# PR9026.net
KiCad netlist of a schematic drawn in EAGLE
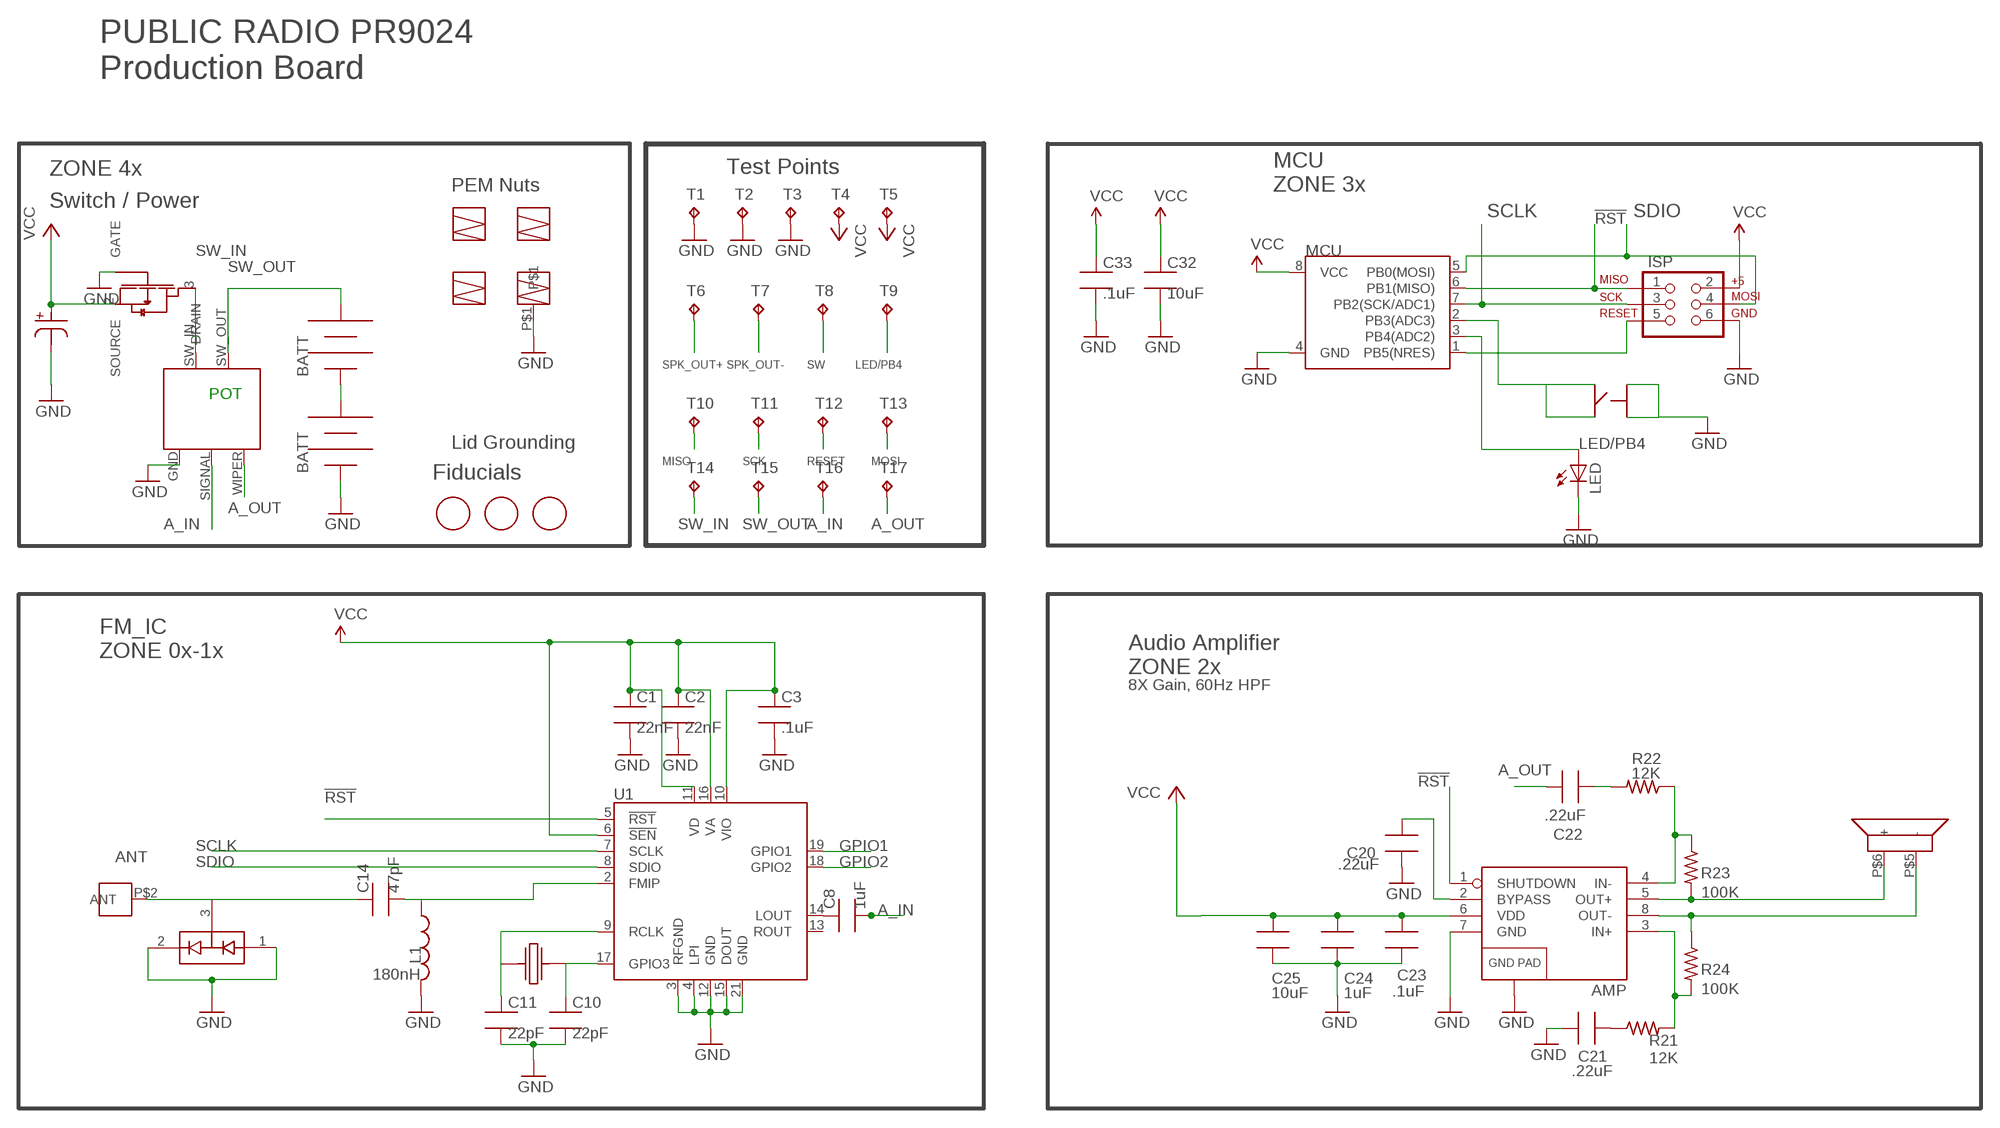
[diagram p0: schematic, sheet 1]

(export (version "E")
  (design (tool "Eeschema 10.0.6"))
  (components
    (comp (ref "AMP")
      (value "TPA6203A1")
      (footprint "eagle-import:8-MSOP")
      (libsource (lib "eagle-import") (part "TPA6203A1"))
    )
    (comp (ref "ANT_MOUNT")
      (value "DNP")
      (footprint "eagle-import:PEM_M3")
      (libsource (lib "eagle-import") (part "M3_PEMNUT"))
    )
    (comp (ref "C1")
      (value "22nF")
      (footprint "eagle-import:0603_CPL")
      (fields
        (field (name "MFG_PN") "CL10B223KB8NNNC")
        (field (name "TOL") "10%")
        (field (name "VOLTAGE") "16V")
      )
      (libsource (lib "eagle-import") (part "C_SMT_0603_CPL"))
    )
    (comp (ref "C2")
      (value "22nF")
      (footprint "eagle-import:0603_CPL")
      (fields
        (field (name "MFG_PN") "CL10B223KB8NNNC")
        (field (name "TOL") "10%")
        (field (name "VOLTAGE") "16V")
      )
      (libsource (lib "eagle-import") (part "C_SMT_0603_CPL"))
    )
    (comp (ref "C3")
      (value ".1uF")
      (footprint "eagle-import:0603_CPL")
      (fields
        (field (name "MFG_PN") "CL10B104KB8SFNC")
        (field (name "TOL") "10%")
        (field (name "VOLTAGE") "16V")
      )
      (libsource (lib "eagle-import") (part "C_SMT_0603_CPL"))
    )
    (comp (ref "C8")
      (value "1uF")
      (footprint "eagle-import:0603_CPL")
      (fields
        (field (name "MFG_PN") "CL10B105KP8NNNC")
        (field (name "TOL") "10%")
        (field (name "VOLTAGE") "10V")
      )
      (libsource (lib "eagle-import") (part "C_SMT_0603_CPL"))
    )
    (comp (ref "C10")
      (value "22pF")
      (footprint "eagle-import:0603_CPL")
      (fields
        (field (name "MFG_PN") "C1608C0G1H220J080AA")
        (field (name "TOL") "5%")
        (field (name "VOLTAGE") "50V")
      )
      (libsource (lib "eagle-import") (part "C_SMT_0603_CPL"))
    )
    (comp (ref "C11")
      (value "22pF")
      (footprint "eagle-import:0603_CPL")
      (fields
        (field (name "MFG_PN") "C1608C0G1H220J080AA")
        (field (name "TOL") "5%")
        (field (name "VOLTAGE") "50V")
      )
      (libsource (lib "eagle-import") (part "C_SMT_0603_CPL"))
    )
    (comp (ref "C14")
      (value "47pF")
      (footprint "eagle-import:0603_CPL")
      (fields
        (field (name "MFG_PN") "CL10C470JB8NCNC")
        (field (name "TOL") "5%")
        (field (name "VOLTAGE") "50V")
      )
      (libsource (lib "eagle-import") (part "C_SMT_0603_CPL"))
    )
    (comp (ref "C20")
      (value ".22uF")
      (footprint "eagle-import:0603_CPL")
      (fields
        (field (name "MFG_PN") "C1608X7R1C224K080AC")
        (field (name "TOL") "10%")
        (field (name "VOLTAGE") "16V")
      )
      (libsource (lib "eagle-import") (part "C_SMT_0603_CPL"))
    )
    (comp (ref "C21")
      (value ".22uF")
      (footprint "eagle-import:0603_CPL")
      (fields
        (field (name "MFG_PN") "C1608X7R1C224K080AC")
        (field (name "TOL") "10%")
        (field (name "VOLTAGE") "16V")
      )
      (libsource (lib "eagle-import") (part "C_SMT_0603_CPL"))
    )
    (comp (ref "C22")
      (value ".22uF")
      (footprint "eagle-import:0603_CPL")
      (fields
        (field (name "MFG_PN") "C1608X7R1C224K080AC")
        (field (name "TOL") "10%")
        (field (name "VOLTAGE") "16V")
      )
      (libsource (lib "eagle-import") (part "C_SMT_0603_CPL"))
    )
    (comp (ref "C23")
      (value ".1uF")
      (footprint "eagle-import:0603_CPL")
      (fields
        (field (name "MFG_PN") "CL10B104KB8SFNC")
        (field (name "TOL") "10%")
        (field (name "VOLTAGE") "16V")
      )
      (libsource (lib "eagle-import") (part "C_SMT_0603_CPL"))
    )
    (comp (ref "C24")
      (value "1uF")
      (footprint "eagle-import:0603_CPL")
      (fields
        (field (name "MFG_PN") "CL10B105KP8NNNC")
        (field (name "TOL") "10%")
        (field (name "VOLTAGE") "10V")
      )
      (libsource (lib "eagle-import") (part "C_SMT_0603_CPL"))
    )
    (comp (ref "C25")
      (value "10uF")
      (footprint "eagle-import:0603_CPL")
      (fields
        (field (name "MFG_PN") "CL10A106MQ8NNNC")
        (field (name "TOL") "20%")
        (field (name "VOLTAGE") "6.3V")
      )
      (libsource (lib "eagle-import") (part "C_SMT_0603_CPL"))
    )
    (comp (ref "C32")
      (value "10uF")
      (footprint "eagle-import:0603_CPL")
      (fields
        (field (name "MFG_PN") "CL10A106MQ8NNNC")
        (field (name "TOL") "20%")
        (field (name "VOLTAGE") "6.3V")
      )
      (libsource (lib "eagle-import") (part "C_SMT_0603_CPL"))
    )
    (comp (ref "C33")
      (value ".1uF")
      (footprint "eagle-import:0603_CPL")
      (fields
        (field (name "MFG_PN") "CL10B104KB8SFNC")
        (field (name "TOL") "10%")
        (field (name "VOLTAGE") "16V")
      )
      (libsource (lib "eagle-import") (part "C_SMT_0603_CPL"))
    )
    (comp (ref "C40")
      (value "220uF")
      (footprint "eagle-import:NICHICON_UD_63")
      (fields (field (name "TOL") "20%") (field (name "VOLTAGE") "16V"))
      (libsource (lib "eagle-import") (part "NICHICON_SERIESUD"))
    )
    (comp (ref "D1")
      (value "BAV99")
      (footprint "eagle-import:SOT23_CPL")
      (fields (field (name "MFG_PN") "BAV99,215"))
      (libsource (lib "eagle-import") (part "BAV99"))
    )
    (comp (ref "FET1")
      (value "AO3435")
      (footprint "eagle-import:SOT23_CPL")
      (fields (field (name "MFG_PN") "AO3435"))
      (libsource (lib "eagle-import") (part "AO3435"))
    )
    (comp (ref "ISP")
      (value "AVR_SPI_PRG_6NS")
      (footprint "eagle-import:2X3-NS")
      (libsource (lib "eagle-import") (part "AVR_SPI_PRG_6NS"))
    )
    (comp (ref "JP5")
      (value "BK-92_MPD_AA_BATT_CLIP")
      (footprint "eagle-import:BK92_AA_BATT")
      (fields (field (name "MFG_PN") "2 of BK92 - supplied by CL Labs"))
      (libsource (lib "eagle-import") (part "BK-92_MPD_AA_BATT_CLIP"))
    )
    (comp (ref "JP6")
      (value "BK-92_MPD_AA_BATT_CLIP")
      (footprint "eagle-import:BK92_AA_BATT")
      (fields (field (name "MFG_PN") "2 of BK92 - supplied by CL Labs"))
      (libsource (lib "eagle-import") (part "BK-92_MPD_AA_BATT_CLIP"))
    )
    (comp (ref "L1")
      (value "180nH")
      (footprint "eagle-import:0805_ADAFRUIT")
      (fields
        (field (name "CURRENT") "400mA")
        (field (name "DCR") "640m")
        (field (name "MFG_PN") "AISC-0805-R18J-T")
        (field (name "TOL") "5%")
      )
      (libsource (lib "eagle-import") (part "L_SMT_0805_ADAFRUIT"))
    )
    (comp (ref "LED")
      (value "HSMC-C265_REVERSE_MOUNT_LED")
      (footprint "eagle-import:HSMC-C265_REVERSE_MOUN_LED")
      (libsource (lib "eagle-import") (part "HSMC-C265_REVERSE_MOUNT_LED"))
    )
    (comp (ref "MARK1")
      (value "FIDUCIAL")
      (footprint "eagle-import:FIDUCIAL_1MM")
      (libsource (lib "eagle-import") (part "FIDUCIAL"))
    )
    (comp (ref "MARK2")
      (value "FIDUCIAL")
      (footprint "eagle-import:FIDUCIAL_1MM")
      (libsource (lib "eagle-import") (part "FIDUCIAL"))
    )
    (comp (ref "MARK3")
      (value "FIDUCIAL")
      (footprint "eagle-import:FIDUCIAL_1MM")
      (libsource (lib "eagle-import") (part "FIDUCIAL"))
    )
    (comp (ref "MCU")
      (value "ATTINY45TINY45-20-SMT")
      (footprint "eagle-import:8-SOIC")
      (libsource (lib "eagle-import") (part "ATTINY45TINY45-20-SMT"))
    )
    (comp (ref "R1")
      (value "VOLUME_POT")
      (footprint "eagle-import:H17112NS_A10K_L20F-002")
      (libsource (lib "eagle-import") (part "VOLUME_POT"))
    )
    (comp (ref "R21")
      (value "12K")
      (footprint "eagle-import:0603_CPL")
      (fields
        (field (name "MFG_PN") "RC0603FR-0712KL")
        (field (name "POWER") "1/10W")
        (field (name "TOL") "1%")
      )
      (libsource (lib "eagle-import") (part "R_SMT_R0603_CPL"))
    )
    (comp (ref "R22")
      (value "12K")
      (footprint "eagle-import:0603_CPL")
      (fields
        (field (name "MFG_PN") "RC0603FR-0712KL")
        (field (name "POWER") "1/10W")
        (field (name "TOL") "1%")
      )
      (libsource (lib "eagle-import") (part "R_SMT_R0603_CPL"))
    )
    (comp (ref "R23")
      (value "100K")
      (footprint "eagle-import:0603_CPL")
      (fields
        (field (name "MFG_PN") "ERJ-3EKF1003V")
        (field (name "POWER") "1/10W")
        (field (name "TOL") "1%")
      )
      (libsource (lib "eagle-import") (part "R_SMT_R0603_CPL"))
    )
    (comp (ref "R24")
      (value "100K")
      (footprint "eagle-import:0603_CPL")
      (fields
        (field (name "MFG_PN") "ERJ-3EKF1003V")
        (field (name "POWER") "1/10W")
        (field (name "TOL") "1%")
      )
      (libsource (lib "eagle-import") (part "R_SMT_R0603_CPL"))
    )
    (comp (ref "SPKR_PLACE")
      (value "PR2024_SPKR_SMD")
      (footprint "eagle-import:PR2024_SPKR_PLACE(SMD)")
      (libsource (lib "eagle-import") (part "PR2024_SPKR_SMD"))
    )
    (comp (ref "SW1")
      (value "C&K_PTS645")
      (footprint "eagle-import:C&K_PTS645_SMT")
      (libsource (lib "eagle-import") (part "C&K_PTS645"))
    )
    (comp (ref "T1")
      (value "TPTP20R")
      (footprint "eagle-import:TP20R")
      (libsource (lib "eagle-import") (part "TPTP20R"))
    )
    (comp (ref "T2")
      (value "TPTP20R")
      (footprint "eagle-import:TP20R")
      (libsource (lib "eagle-import") (part "TPTP20R"))
    )
    (comp (ref "T3")
      (value "TPTP20R")
      (footprint "eagle-import:TP20R")
      (libsource (lib "eagle-import") (part "TPTP20R"))
    )
    (comp (ref "T4")
      (value "TPTP20R")
      (footprint "eagle-import:TP20R")
      (libsource (lib "eagle-import") (part "TPTP20R"))
    )
    (comp (ref "T5")
      (value "TPTP20R")
      (footprint "eagle-import:TP20R")
      (libsource (lib "eagle-import") (part "TPTP20R"))
    )
    (comp (ref "T6")
      (value "TPTP20R")
      (footprint "eagle-import:TP20R")
      (libsource (lib "eagle-import") (part "TPTP20R"))
    )
    (comp (ref "T7")
      (value "TPTP20R")
      (footprint "eagle-import:TP20R")
      (libsource (lib "eagle-import") (part "TPTP20R"))
    )
    (comp (ref "T8")
      (value "TPTP20R")
      (footprint "eagle-import:TP20R")
      (libsource (lib "eagle-import") (part "TPTP20R"))
    )
    (comp (ref "T9")
      (value "TPTP20R")
      (footprint "eagle-import:TP20R")
      (libsource (lib "eagle-import") (part "TPTP20R"))
    )
    (comp (ref "T10")
      (value "TPTP20R")
      (footprint "eagle-import:TP20R")
      (libsource (lib "eagle-import") (part "TPTP20R"))
    )
    (comp (ref "T11")
      (value "TPTP20R")
      (footprint "eagle-import:TP20R")
      (libsource (lib "eagle-import") (part "TPTP20R"))
    )
    (comp (ref "T12")
      (value "TPTP20R")
      (footprint "eagle-import:TP20R")
      (libsource (lib "eagle-import") (part "TPTP20R"))
    )
    (comp (ref "T13")
      (value "TPTP20R")
      (footprint "eagle-import:TP20R")
      (libsource (lib "eagle-import") (part "TPTP20R"))
    )
    (comp (ref "T14")
      (value "TPTP20R")
      (footprint "eagle-import:TP20R")
      (libsource (lib "eagle-import") (part "TPTP20R"))
    )
    (comp (ref "T15")
      (value "TPTP20R")
      (footprint "eagle-import:TP20R")
      (libsource (lib "eagle-import") (part "TPTP20R"))
    )
    (comp (ref "T16")
      (value "TPTP20R")
      (footprint "eagle-import:TP20R")
      (libsource (lib "eagle-import") (part "TPTP20R"))
    )
    (comp (ref "T17")
      (value "TPTP20R")
      (footprint "eagle-import:TP20R")
      (libsource (lib "eagle-import") (part "TPTP20R"))
    )
    (comp (ref "U$2")
      (value "PEM_SMT")
      (footprint "eagle-import:PEM_SMT")
      (libsource (lib "eagle-import") (part "PEM_SMT"))
    )
    (comp (ref "U$3")
      (value "PEM_SMT")
      (footprint "eagle-import:PEM_SMT")
      (libsource (lib "eagle-import") (part "PEM_SMT"))
    )
    (comp (ref "U$4")
      (value "PEM_SMT")
      (footprint "eagle-import:PEM_SMT")
      (libsource (lib "eagle-import") (part "PEM_SMT"))
    )
    (comp (ref "U$5")
      (value "PEM_M3_SMT_W/PIN")
      (footprint "eagle-import:PEM_SMT")
      (libsource (lib "eagle-import") (part "PEM_M3_SMT_W/PIN"))
    )
    (comp (ref "U1")
      (value "SI4702-C19-GMR")
      (footprint "eagle-import:SI470X_20_QFN")
      (fields (field (name "MFG_PN") "Si4702 C19 GM - supplied by CL Labs"))
      (libsource (lib "eagle-import") (part "SI4702-C19-GMR"))
    )
    (comp (ref "X1")
      (value "ABS25XTAL")
      (footprint "eagle-import:4-SOJ")
      (libsource (lib "eagle-import") (part "ABS25XTAL"))
    )
  )
  (nets
    (net (code "1") (name "/ANT") (class "Default")
      (node (ref "ANT_MOUNT") (pin "P$2") (pinfunction "ANT_P$2") (pintype "bidirectional"))
      (node (ref "C14") (pin "1") (pinfunction "1_1") (pintype "passive"))
      (node (ref "D1") (pin "3") (pinfunction "COM_3") (pintype "bidirectional"))
    )
    (net (code "2") (name "/A_IN") (class "Default")
      (node (ref "C8") (pin "2") (pinfunction "2_2") (pintype "passive"))
      (node (ref "R1") (pin "SIGNAL") (pinfunction "SIGNAL_SIGNAL") (pintype "bidirectional"))
      (node (ref "T16") (pin "TP") (pinfunction "TP_TP") (pintype "input"))
    )
    (net (code "3") (name "/A_OUT") (class "Default")
      (node (ref "C22") (pin "2") (pinfunction "2_2") (pintype "passive"))
      (node (ref "R1") (pin "WIPER") (pinfunction "WIPER_WIPER") (pintype "bidirectional"))
      (node (ref "T17") (pin "TP") (pinfunction "TP_TP") (pintype "input"))
    )
    (net (code "4") (name "/GPIO1") (class "Default")
      (node (ref "U1") (pin "19") (pinfunction "GPIO1_19") (pintype "bidirectional"))
    )
    (net (code "5") (name "/GPIO2") (class "Default")
      (node (ref "U1") (pin "18") (pinfunction "GPIO2_18") (pintype "bidirectional"))
    )
    (net (code "6") (name "/LED{slash}PB4") (class "Default")
      (node (ref "LED") (pin "P$1") (pinfunction "A_P$1") (pintype "passive"))
      (node (ref "MCU") (pin "3") (pinfunction "PB4(ADC2)_3") (pintype "bidirectional"))
      (node (ref "T9") (pin "TP") (pinfunction "TP_TP") (pintype "input"))
    )
    (net (code "7") (name "/RESET") (class "Default")
      (node (ref "ISP") (pin "5") (pinfunction "5_5") (pintype "passive"))
      (node (ref "MCU") (pin "1") (pinfunction "PB5(NRES)_1") (pintype "bidirectional"))
      (node (ref "T12") (pin "TP") (pinfunction "TP_TP") (pintype "input"))
    )
    (net (code "8") (name "/SCLK") (class "Default")
      (node (ref "ISP") (pin "3") (pinfunction "3_3") (pintype "passive"))
      (node (ref "MCU") (pin "7") (pinfunction "PB2(SCK/ADC1)_7") (pintype "bidirectional"))
      (node (ref "T11") (pin "TP") (pinfunction "TP_TP") (pintype "input"))
      (node (ref "U1") (pin "7") (pinfunction "SCLK_7") (pintype "bidirectional"))
    )
    (net (code "9") (name "/SDIO") (class "Default")
      (node (ref "ISP") (pin "4") (pinfunction "4_4") (pintype "passive"))
      (node (ref "MCU") (pin "5") (pinfunction "PB0(MOSI)_5") (pintype "bidirectional"))
      (node (ref "T13") (pin "TP") (pinfunction "TP_TP") (pintype "input"))
      (node (ref "U1") (pin "8") (pinfunction "SDIO_8") (pintype "bidirectional"))
    )
    (net (code "10") (name "/SPK_OUT+") (class "Default")
      (node (ref "AMP") (pin "5") (pinfunction "OUT+_5") (pintype "bidirectional"))
      (node (ref "R23") (pin "2") (pinfunction "2_2") (pintype "passive"))
      (node (ref "SPKR_PLACE") (pin "P$6") (pinfunction "+_P$6") (pintype "bidirectional"))
      (node (ref "T6") (pin "TP") (pinfunction "TP_TP") (pintype "input"))
    )
    (net (code "11") (name "/SPK_OUT-") (class "Default")
      (node (ref "AMP") (pin "8") (pinfunction "OUT-_8") (pintype "bidirectional"))
      (node (ref "R24") (pin "1") (pinfunction "1_1") (pintype "passive"))
      (node (ref "SPKR_PLACE") (pin "P$5") (pinfunction "-_P$5") (pintype "bidirectional"))
      (node (ref "T7") (pin "TP") (pinfunction "TP_TP") (pintype "input"))
    )
    (net (code "12") (name "/SW") (class "Default")
      (node (ref "MCU") (pin "2") (pinfunction "PB3(ADC3)_2") (pintype "bidirectional"))
      (node (ref "SW1") (pin "P$3") (pinfunction "P$3_P$3") (pintype "bidirectional"))
      (node (ref "SW1") (pin "P$4") (pinfunction "P$4_P$4") (pintype "bidirectional"))
      (node (ref "T8") (pin "TP") (pinfunction "TP_TP") (pintype "input"))
    )
    (net (code "13") (name "/SW_IN") (class "Default")
      (node (ref "FET1") (pin "3") (pinfunction "DRAIN_3") (pintype "bidirectional"))
      (node (ref "R1") (pin "SW_IN") (pinfunction "SW_IN_SW_IN") (pintype "bidirectional"))
      (node (ref "T14") (pin "TP") (pinfunction "TP_TP") (pintype "input"))
    )
    (net (code "14") (name "/SW_OUT") (class "Default")
      (node (ref "JP5") (pin "POS") (pinfunction "POS_POS") (pintype "bidirectional"))
      (node (ref "JP5") (pin "POS@2") (pinfunction "POS_POS@2") (pintype "bidirectional"))
      (node (ref "R1") (pin "SW_OUT") (pinfunction "SW_OUT_SW_OUT") (pintype "bidirectional"))
      (node (ref "T15") (pin "TP") (pinfunction "TP_TP") (pintype "input"))
    )
    (net (code "15") (name "/~{RST}") (class "Default")
      (node (ref "AMP") (pin "1") (pinfunction "SHUTDOWN_1") (pintype "input"))
      (node (ref "ISP") (pin "1") (pinfunction "1_1") (pintype "passive"))
      (node (ref "MCU") (pin "6") (pinfunction "PB1(MISO)_6") (pintype "bidirectional"))
      (node (ref "T10") (pin "TP") (pinfunction "TP_TP") (pintype "input"))
      (node (ref "U1") (pin "5") (pinfunction "~{RST}_5") (pintype "bidirectional"))
    )
    (net (code "16") (name "GND") (class "Default")
      (node (ref "AMP") (pin "7") (pinfunction "GND_7") (pintype "power_in"))
      (node (ref "AMP") (pin "9") (pinfunction "GND_9") (pintype "power_in"))
      (node (ref "C1") (pin "2") (pinfunction "2_2") (pintype "passive"))
      (node (ref "C10") (pin "2") (pinfunction "2_2") (pintype "passive"))
      (node (ref "C11") (pin "2") (pinfunction "2_2") (pintype "passive"))
      (node (ref "C2") (pin "2") (pinfunction "2_2") (pintype "passive"))
      (node (ref "C20") (pin "1") (pinfunction "1_1") (pintype "passive"))
      (node (ref "C21") (pin "1") (pinfunction "1_1") (pintype "passive"))
      (node (ref "C23") (pin "2") (pinfunction "2_2") (pintype "passive"))
      (node (ref "C24") (pin "2") (pinfunction "2_2") (pintype "passive"))
      (node (ref "C25") (pin "2") (pinfunction "2_2") (pintype "passive"))
      (node (ref "C3") (pin "2") (pinfunction "2_2") (pintype "passive"))
      (node (ref "C32") (pin "2") (pinfunction "2_2") (pintype "passive"))
      (node (ref "C33") (pin "2") (pinfunction "2_2") (pintype "passive"))
      (node (ref "C40") (pin "P$2") (pinfunction "P$2_P$2") (pintype "bidirectional"))
      (node (ref "D1") (pin "1") (pinfunction "A1_1") (pintype "bidirectional"))
      (node (ref "D1") (pin "2") (pinfunction "C2_2") (pintype "bidirectional"))
      (node (ref "FET1") (pin "1") (pinfunction "GATE_1") (pintype "bidirectional"))
      (node (ref "ISP") (pin "6") (pinfunction "6_6") (pintype "passive"))
      (node (ref "JP6") (pin "NEG") (pinfunction "NEG_NEG") (pintype "bidirectional"))
      (node (ref "JP6") (pin "NEG@2") (pinfunction "NEG_NEG@2") (pintype "bidirectional"))
      (node (ref "L1") (pin "2") (pinfunction "2_2") (pintype "passive"))
      (node (ref "LED") (pin "P$2") (pinfunction "C_P$2") (pintype "passive"))
      (node (ref "MCU") (pin "4") (pinfunction "GND_4") (pintype "bidirectional"))
      (node (ref "R1") (pin "GND") (pinfunction "GND_GND") (pintype "bidirectional"))
      (node (ref "SW1") (pin "P$1") (pinfunction "P$1_P$1") (pintype "bidirectional"))
      (node (ref "SW1") (pin "P$2") (pinfunction "P$2_P$2") (pintype "bidirectional"))
      (node (ref "T1") (pin "TP") (pinfunction "TP_TP") (pintype "input"))
      (node (ref "T2") (pin "TP") (pinfunction "TP_TP") (pintype "input"))
      (node (ref "T3") (pin "TP") (pinfunction "TP_TP") (pintype "input"))
      (node (ref "U$5") (pin "P$1") (pinfunction "P$1_P$1") (pintype "bidirectional"))
      (node (ref "U1") (pin "12") (pinfunction "GND_12") (pintype "bidirectional"))
      (node (ref "U1") (pin "15") (pinfunction "DOUT_15") (pintype "bidirectional"))
      (node (ref "U1") (pin "21") (pinfunction "GND_21") (pintype "bidirectional"))
      (node (ref "U1") (pin "3") (pinfunction "RFGND_3") (pintype "bidirectional"))
      (node (ref "U1") (pin "4") (pinfunction "LPI_4") (pintype "bidirectional"))
    )
    (net (code "17") (name "Net-(AMP-BYPASS)") (class "Default")
      (node (ref "AMP") (pin "2") (pinfunction "BYPASS_2") (pintype "bidirectional"))
      (node (ref "C20") (pin "2") (pinfunction "2_2") (pintype "passive"))
    )
    (net (code "18") (name "Net-(AMP-IN+)") (class "Default")
      (node (ref "AMP") (pin "3") (pinfunction "IN+_3") (pintype "bidirectional"))
      (node (ref "R21") (pin "2") (pinfunction "2_2") (pintype "passive"))
      (node (ref "R24") (pin "2") (pinfunction "2_2") (pintype "passive"))
    )
    (net (code "19") (name "Net-(AMP-IN-)") (class "Default")
      (node (ref "AMP") (pin "4") (pinfunction "IN-_4") (pintype "bidirectional"))
      (node (ref "R22") (pin "1") (pinfunction "1_1") (pintype "passive"))
      (node (ref "R23") (pin "1") (pinfunction "1_1") (pintype "passive"))
    )
    (net (code "20") (name "Net-(C21-Pad2)") (class "Default")
      (node (ref "C21") (pin "2") (pinfunction "2_2") (pintype "passive"))
      (node (ref "R21") (pin "1") (pinfunction "1_1") (pintype "passive"))
    )
    (net (code "21") (name "Net-(C22-Pad1)") (class "Default")
      (node (ref "C22") (pin "1") (pinfunction "1_1") (pintype "passive"))
      (node (ref "R22") (pin "2") (pinfunction "2_2") (pintype "passive"))
    )
    (net (code "22") (name "Net-(JP5-NEG-PadNEG@2)") (class "Default")
      (node (ref "JP5") (pin "NEG") (pinfunction "NEG_NEG") (pintype "bidirectional"))
      (node (ref "JP5") (pin "NEG@2") (pinfunction "NEG_NEG@2") (pintype "bidirectional"))
      (node (ref "JP6") (pin "POS") (pinfunction "POS_POS") (pintype "bidirectional"))
      (node (ref "JP6") (pin "POS@2") (pinfunction "POS_POS@2") (pintype "bidirectional"))
    )
    (net (code "23") (name "Net-(U1-FMIP)") (class "Default")
      (node (ref "C14") (pin "2") (pinfunction "2_2") (pintype "passive"))
      (node (ref "L1") (pin "1") (pinfunction "1_1") (pintype "passive"))
      (node (ref "U1") (pin "2") (pinfunction "FMIP_2") (pintype "bidirectional"))
    )
    (net (code "24") (name "Net-(U1-GPIO3)") (class "Default")
      (node (ref "C10") (pin "1") (pinfunction "1_1") (pintype "passive"))
      (node (ref "U1") (pin "17") (pinfunction "GPIO3_17") (pintype "bidirectional"))
      (node (ref "X1") (pin "P$4") (pinfunction "P$4_P$4") (pintype "bidirectional"))
    )
    (net (code "25") (name "Net-(U1-LOUT)") (class "Default")
      (node (ref "C8") (pin "1") (pinfunction "1_1") (pintype "passive"))
      (node (ref "U1") (pin "14") (pinfunction "LOUT_14") (pintype "bidirectional"))
    )
    (net (code "26") (name "Net-(U1-RCLK)") (class "Default")
      (node (ref "C11") (pin "1") (pinfunction "1_1") (pintype "passive"))
      (node (ref "U1") (pin "9") (pinfunction "RCLK_9") (pintype "bidirectional"))
      (node (ref "X1") (pin "P$1") (pinfunction "P$1_P$1") (pintype "bidirectional"))
    )
    (net (code "27") (name "VCC") (class "Default")
      (node (ref "AMP") (pin "6") (pinfunction "VDD_6") (pintype "power_in"))
      (node (ref "C1") (pin "1") (pinfunction "1_1") (pintype "passive"))
      (node (ref "C2") (pin "1") (pinfunction "1_1") (pintype "passive"))
      (node (ref "C23") (pin "1") (pinfunction "1_1") (pintype "passive"))
      (node (ref "C24") (pin "1") (pinfunction "1_1") (pintype "passive"))
      (node (ref "C25") (pin "1") (pinfunction "1_1") (pintype "passive"))
      (node (ref "C3") (pin "1") (pinfunction "1_1") (pintype "passive"))
      (node (ref "C32") (pin "1") (pinfunction "1_1") (pintype "passive"))
      (node (ref "C33") (pin "1") (pinfunction "1_1") (pintype "passive"))
      (node (ref "C40") (pin "P$1") (pinfunction "P$1_P$1") (pintype "bidirectional"))
      (node (ref "FET1") (pin "2") (pinfunction "SOURCE_2") (pintype "bidirectional"))
      (node (ref "ISP") (pin "2") (pinfunction "2_2") (pintype "passive"))
      (node (ref "MCU") (pin "8") (pinfunction "VCC_8") (pintype "bidirectional"))
      (node (ref "T4") (pin "TP") (pinfunction "TP_TP") (pintype "input"))
      (node (ref "T5") (pin "TP") (pinfunction "TP_TP") (pintype "input"))
      (node (ref "U1") (pin "10") (pinfunction "VIO_10") (pintype "bidirectional"))
      (node (ref "U1") (pin "11") (pinfunction "VD_11") (pintype "bidirectional"))
      (node (ref "U1") (pin "16") (pinfunction "VA_16") (pintype "bidirectional"))
      (node (ref "U1") (pin "6") (pinfunction "~{SEN}_6") (pintype "bidirectional"))
    )
    (net (code "28") (name "unconnected-(U1-ROUT-Pad13)") (class "Default")
      (node (ref "U1") (pin "13") (pinfunction "ROUT_13") (pintype "bidirectional"))
    )
  )
)
